# Lightbox2.net
KiCad netlist of a schematic drawn in EAGLE
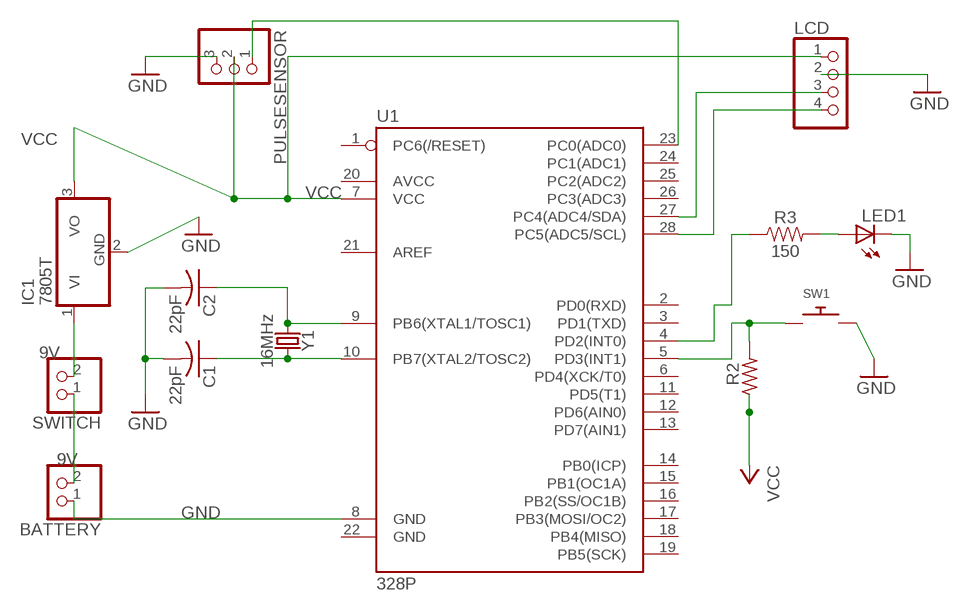
[diagram p0: schematic, sheet 1]

(export (version "E")
  (design (tool "Eeschema 10.0.6"))
  (components
    (comp (ref "BATTERY")
      (value "PINHD-1X2")
      (footprint "eagle-import:1X02")
      (libsource (lib "eagle-import") (part "PINHD-1X2"))
    )
    (comp (ref "C1")
      (value "22pF")
      (footprint "eagle-import:C025-024X044")
      (libsource (lib "eagle-import") (part "C-US025-024X044"))
    )
    (comp (ref "C2")
      (value "22pF")
      (footprint "eagle-import:C025-024X044")
      (libsource (lib "eagle-import") (part "C-US025-024X044"))
    )
    (comp (ref "IC1")
      (value "7805T")
      (footprint "eagle-import:TO220H")
      (libsource (lib "eagle-import") (part "78T05"))
    )
    (comp (ref "LCD")
      (value "PINHD-1X4")
      (footprint "eagle-import:1X04")
      (libsource (lib "eagle-import") (part "PINHD-1X4"))
    )
    (comp (ref "LED1")
      (value "LED5MM")
      (footprint "eagle-import:LED5MM")
      (libsource (lib "eagle-import") (part "LED5MM"))
    )
    (comp (ref "PULSESENSOR")
      (value "PINHD-1X3")
      (footprint "eagle-import:1X03")
      (libsource (lib "eagle-import") (part "PINHD-1X3"))
    )
    (comp (ref "R2")
      (value "R-US_0204/5")
      (footprint "eagle-import:0204_5")
      (libsource (lib "eagle-import") (part "R-US_0204/5"))
    )
    (comp (ref "R3")
      (value "150")
      (footprint "eagle-import:0603")
      (libsource (lib "eagle-import") (part "150OHM-0603-1/10W-1%"))
    )
    (comp (ref "SW1")
      (value "SWITCH_PUSHBUTTONEVQ-PE")
      (footprint "eagle-import:TACT_PANA-EVQ")
      (libsource (lib "eagle-import") (part "SWITCH_PUSHBUTTONEVQ-PE"))
    )
    (comp (ref "SWITCH")
      (value "PINHD-1X2")
      (footprint "eagle-import:1X02")
      (libsource (lib "eagle-import") (part "PINHD-1X2"))
    )
    (comp (ref "U1")
      (value "328P")
      (footprint "eagle-import:DIP28")
      (libsource (lib "eagle-import") (part "ATMEGA328P_PDIP"))
    )
    (comp (ref "Y1")
      (value "16MHz")
      (footprint "eagle-import:HC49US")
      (libsource (lib "eagle-import") (part "CRYSTAL-16MHZPTH-HC49US"))
    )
  )
  (nets
    (net (code "1") (name "/9V") (class "Default")
      (node (ref "BATTERY") (pin "2") (pinfunction "2_2") (pintype "passive"))
      (node (ref "IC1") (pin "1") (pinfunction "VI_1") (pintype "input"))
      (node (ref "SWITCH") (pin "1") (pinfunction "1_1") (pintype "passive"))
      (node (ref "SWITCH") (pin "2") (pinfunction "2_2") (pintype "passive"))
    )
    (net (code "2") (name "GND") (class "Default")
      (node (ref "BATTERY") (pin "1") (pinfunction "1_1") (pintype "passive"))
      (node (ref "C1") (pin "2") (pinfunction "2_2") (pintype "passive"))
      (node (ref "C2") (pin "2") (pinfunction "2_2") (pintype "passive"))
      (node (ref "IC1") (pin "2") (pinfunction "GND_2") (pintype "passive"))
      (node (ref "LCD") (pin "2") (pinfunction "2_2") (pintype "passive"))
      (node (ref "LED1") (pin "K") (pinfunction "C_K") (pintype "passive"))
      (node (ref "PULSESENSOR") (pin "3") (pinfunction "3_3") (pintype "passive"))
      (node (ref "SW1") (pin "P$2") (pinfunction "P$2_P$2") (pintype "passive"))
      (node (ref "U1") (pin "8") (pinfunction "GND_8") (pintype "bidirectional"))
    )
    (net (code "3") (name "Net-(LED1-PadA)") (class "Default")
      (node (ref "LED1") (pin "A") (pinfunction "A_A") (pintype "passive"))
      (node (ref "R3") (pin "2") (pinfunction "2_2") (pintype "passive"))
    )
    (net (code "4") (name "Net-(U1-PB6(XTAL1{slash}TOSC1))") (class "Default")
      (node (ref "C2") (pin "1") (pinfunction "1_1") (pintype "passive"))
      (node (ref "U1") (pin "9") (pinfunction "PB6(XTAL1/TOSC1)_9") (pintype "bidirectional"))
      (node (ref "Y1") (pin "1") (pinfunction "1_1") (pintype "passive"))
    )
    (net (code "5") (name "Net-(U1-PB7(XTAL2{slash}TOSC2))") (class "Default")
      (node (ref "C1") (pin "1") (pinfunction "1_1") (pintype "passive"))
      (node (ref "U1") (pin "10") (pinfunction "PB7(XTAL2/TOSC2)_10") (pintype "bidirectional"))
      (node (ref "Y1") (pin "2") (pinfunction "2_2") (pintype "passive"))
    )
    (net (code "6") (name "Net-(U1-PC0(ADC0))") (class "Default")
      (node (ref "PULSESENSOR") (pin "1") (pinfunction "1_1") (pintype "passive"))
      (node (ref "U1") (pin "23") (pinfunction "PC0(ADC0)_23") (pintype "bidirectional"))
    )
    (net (code "7") (name "Net-(U1-PC4(ADC4{slash}SDA))") (class "Default")
      (node (ref "LCD") (pin "3") (pinfunction "3_3") (pintype "passive"))
      (node (ref "U1") (pin "27") (pinfunction "PC4(ADC4/SDA)_27") (pintype "bidirectional"))
    )
    (net (code "8") (name "Net-(U1-PC5(ADC5{slash}SCL))") (class "Default")
      (node (ref "LCD") (pin "4") (pinfunction "4_4") (pintype "passive"))
      (node (ref "U1") (pin "28") (pinfunction "PC5(ADC5/SCL)_28") (pintype "bidirectional"))
    )
    (net (code "9") (name "Net-(U1-PD2(INT0))") (class "Default")
      (node (ref "R3") (pin "1") (pinfunction "1_1") (pintype "passive"))
      (node (ref "U1") (pin "4") (pinfunction "PD2(INT0)_4") (pintype "bidirectional"))
    )
    (net (code "10") (name "Net-(U1-PD3(INT1))") (class "Default")
      (node (ref "R2") (pin "2") (pinfunction "2_2") (pintype "passive"))
      (node (ref "SW1") (pin "P$1") (pinfunction "P$1_P$1") (pintype "passive"))
      (node (ref "U1") (pin "5") (pinfunction "PD3(INT1)_5") (pintype "bidirectional"))
    )
    (net (code "11") (name "VCC") (class "Default")
      (node (ref "IC1") (pin "3") (pinfunction "VO_3") (pintype "passive"))
      (node (ref "LCD") (pin "1") (pinfunction "1_1") (pintype "passive"))
      (node (ref "PULSESENSOR") (pin "2") (pinfunction "2_2") (pintype "passive"))
      (node (ref "R2") (pin "1") (pinfunction "1_1") (pintype "passive"))
      (node (ref "U1") (pin "7") (pinfunction "VCC_7") (pintype "bidirectional"))
    )
    (net (code "12") (name "unconnected-(U1-AREF-Pad21)") (class "Default")
      (node (ref "U1") (pin "21") (pinfunction "AREF_21") (pintype "bidirectional"))
    )
    (net (code "13") (name "unconnected-(U1-AVCC-Pad20)") (class "Default")
      (node (ref "U1") (pin "20") (pinfunction "AVCC_20") (pintype "bidirectional"))
    )
    (net (code "14") (name "unconnected-(U1-GND-Pad22)") (class "Default")
      (node (ref "U1") (pin "22") (pinfunction "GND_22") (pintype "bidirectional"))
    )
    (net (code "15") (name "unconnected-(U1-PB0(ICP)-Pad14)") (class "Default")
      (node (ref "U1") (pin "14") (pinfunction "PB0(ICP)_14") (pintype "bidirectional"))
    )
    (net (code "16") (name "unconnected-(U1-PB1(OC1A)-Pad15)") (class "Default")
      (node (ref "U1") (pin "15") (pinfunction "PB1(OC1A)_15") (pintype "bidirectional"))
    )
    (net (code "17") (name "unconnected-(U1-PB2(SS{slash}OC1B)-Pad16)") (class "Default")
      (node (ref "U1") (pin "16") (pinfunction "PB2(SS/OC1B)_16") (pintype "bidirectional"))
    )
    (net (code "18") (name "unconnected-(U1-PB3(MOSI{slash}OC2)-Pad17)") (class "Default")
      (node (ref "U1") (pin "17") (pinfunction "PB3(MOSI/OC2)_17") (pintype "bidirectional"))
    )
    (net (code "19") (name "unconnected-(U1-PB4(MISO)-Pad18)") (class "Default")
      (node (ref "U1") (pin "18") (pinfunction "PB4(MISO)_18") (pintype "bidirectional"))
    )
    (net (code "20") (name "unconnected-(U1-PB5(SCK)-Pad19)") (class "Default")
      (node (ref "U1") (pin "19") (pinfunction "PB5(SCK)_19") (pintype "bidirectional"))
    )
    (net (code "21") (name "unconnected-(U1-PC1(ADC1)-Pad24)") (class "Default")
      (node (ref "U1") (pin "24") (pinfunction "PC1(ADC1)_24") (pintype "bidirectional"))
    )
    (net (code "22") (name "unconnected-(U1-PC2(ADC2)-Pad25)") (class "Default")
      (node (ref "U1") (pin "25") (pinfunction "PC2(ADC2)_25") (pintype "bidirectional"))
    )
    (net (code "23") (name "unconnected-(U1-PC3(ADC3)-Pad26)") (class "Default")
      (node (ref "U1") (pin "26") (pinfunction "PC3(ADC3)_26") (pintype "bidirectional"))
    )
    (net (code "24") (name "unconnected-(U1-PC6({slash}RESET)-Pad1)") (class "Default")
      (node (ref "U1") (pin "1") (pinfunction "PC6(/RESET)_1") (pintype "bidirectional"))
    )
    (net (code "25") (name "unconnected-(U1-PD0(RXD)-Pad2)") (class "Default")
      (node (ref "U1") (pin "2") (pinfunction "PD0(RXD)_2") (pintype "bidirectional"))
    )
    (net (code "26") (name "unconnected-(U1-PD1(TXD)-Pad3)") (class "Default")
      (node (ref "U1") (pin "3") (pinfunction "PD1(TXD)_3") (pintype "bidirectional"))
    )
    (net (code "27") (name "unconnected-(U1-PD4(XCK{slash}T0)-Pad6)") (class "Default")
      (node (ref "U1") (pin "6") (pinfunction "PD4(XCK/T0)_6") (pintype "bidirectional"))
    )
    (net (code "28") (name "unconnected-(U1-PD5(T1)-Pad11)") (class "Default")
      (node (ref "U1") (pin "11") (pinfunction "PD5(T1)_11") (pintype "bidirectional"))
    )
    (net (code "29") (name "unconnected-(U1-PD6(AIN0)-Pad12)") (class "Default")
      (node (ref "U1") (pin "12") (pinfunction "PD6(AIN0)_12") (pintype "bidirectional"))
    )
    (net (code "30") (name "unconnected-(U1-PD7(AIN1)-Pad13)") (class "Default")
      (node (ref "U1") (pin "13") (pinfunction "PD7(AIN1)_13") (pintype "bidirectional"))
    )
  )
)
